# car_v6.net
KiCad netlist of a schematic drawn in EAGLE
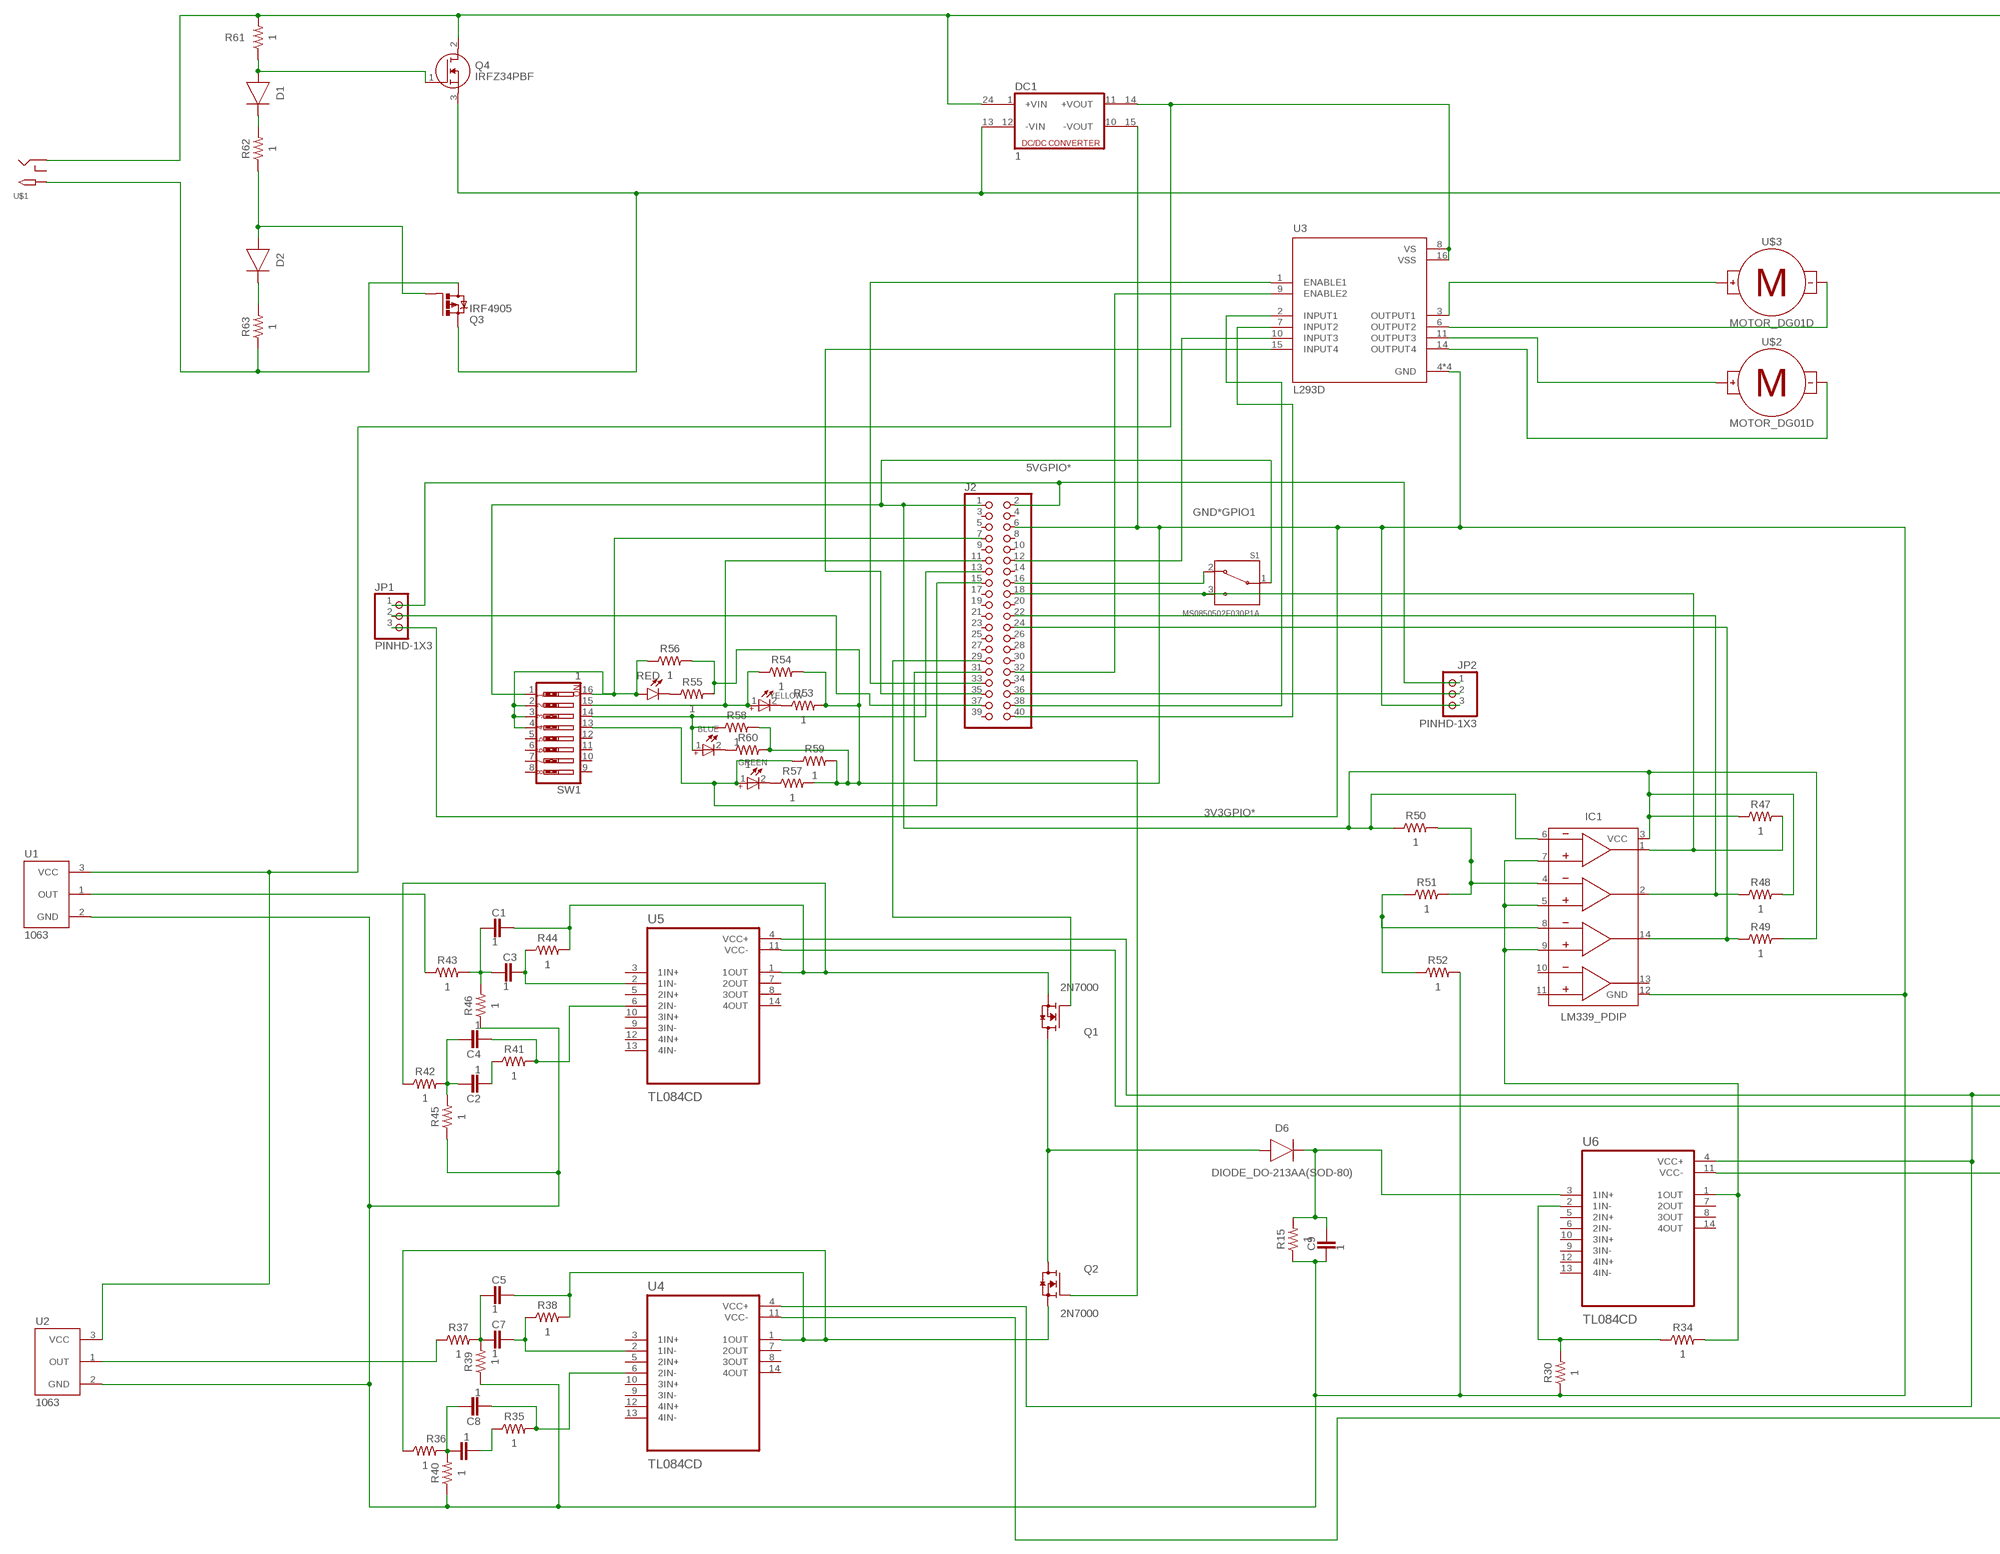
[diagram p0: schematic, sheet 1, part 1 of 2]
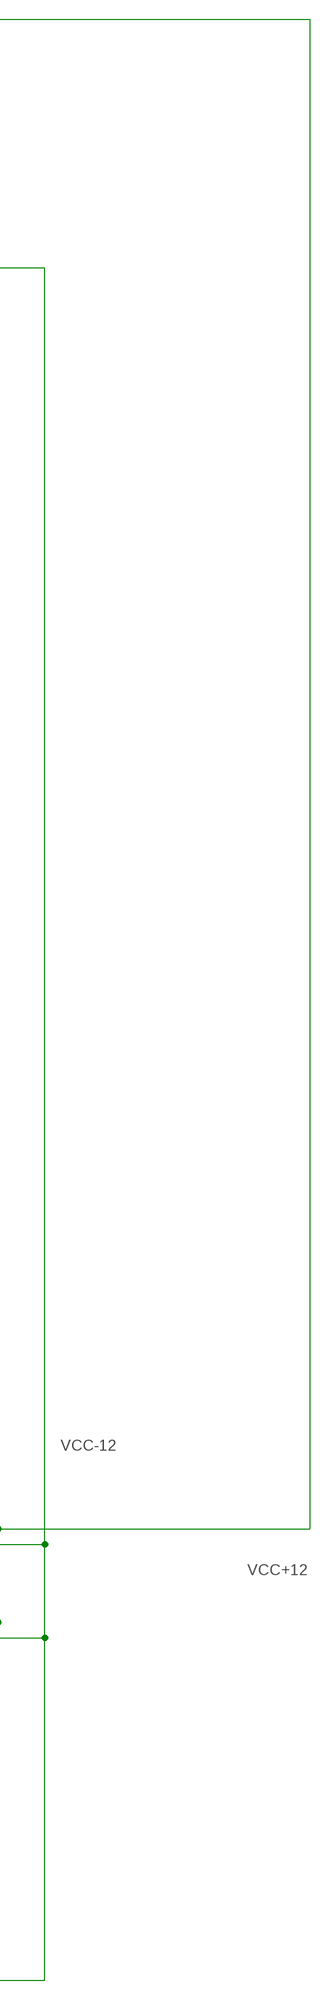
[diagram p1: schematic, sheet 1, part 2 of 2]

(export (version "E")
  (design (tool "Eeschema 10.0.6"))
  (components
    (comp (ref "BLUE")
      (value "WL-TMRC_5MM_WITHOUTSTOPPER")
      (footprint "eagle-import:WL-TMRC_5MM")
      (fields (field (name "MF") "Wurth Electronics") (field (name "MP") "151051BS04000"))
      (libsource (lib "eagle-import") (part "WL-TMRC_5MM_WITHOUTSTOPPER"))
    )
    (comp (ref "C1")
      (value "1")
      (footprint "eagle-import:CAPC1005X60")
      (libsource (lib "eagle-import") (part "CAPACITORCHIP-0402(1005-METRIC)_"))
    )
    (comp (ref "C2")
      (value "1")
      (footprint "eagle-import:CAPC1005X60")
      (libsource (lib "eagle-import") (part "CAPACITORCHIP-0402(1005-METRIC)_"))
    )
    (comp (ref "C3")
      (value "1")
      (footprint "eagle-import:CAPC1005X60")
      (libsource (lib "eagle-import") (part "CAPACITORCHIP-0402(1005-METRIC)_"))
    )
    (comp (ref "C4")
      (value "1")
      (footprint "eagle-import:CAPC1005X60")
      (libsource (lib "eagle-import") (part "CAPACITORCHIP-0402(1005-METRIC)_"))
    )
    (comp (ref "C5")
      (value "1")
      (footprint "eagle-import:CAPC1005X60")
      (libsource (lib "eagle-import") (part "CAPACITORCHIP-0402(1005-METRIC)_"))
    )
    (comp (ref "C6")
      (value "1")
      (footprint "eagle-import:CAPC1005X60")
      (libsource (lib "eagle-import") (part "CAPACITORCHIP-0402(1005-METRIC)_"))
    )
    (comp (ref "C7")
      (value "1")
      (footprint "eagle-import:CAPC1005X60")
      (libsource (lib "eagle-import") (part "CAPACITORCHIP-0402(1005-METRIC)_"))
    )
    (comp (ref "C8")
      (value "1")
      (footprint "eagle-import:CAPC1005X60")
      (libsource (lib "eagle-import") (part "CAPACITORCHIP-0402(1005-METRIC)_"))
    )
    (comp (ref "C9")
      (value "1")
      (footprint "eagle-import:CAPC1005X60")
      (libsource (lib "eagle-import") (part "CAPACITORCHIP-0402(1005-METRIC)_"))
    )
    (comp (ref "D1")
      (value "DIODE_DO-213AA(SOD-80)")
      (footprint "eagle-import:DIOMELF3516")
      (libsource (lib "eagle-import") (part "DIODEDO-213AA(SOD-80)_"))
    )
    (comp (ref "D2")
      (value "DIODE_DO-213AA(SOD-80)")
      (footprint "eagle-import:DIOMELF3516")
      (libsource (lib "eagle-import") (part "DIODEDO-213AA(SOD-80)_"))
    )
    (comp (ref "D6")
      (value "DIODE_DO-213AA(SOD-80)")
      (footprint "eagle-import:DIOMELF3516")
      (libsource (lib "eagle-import") (part "DIODEDO-213AA(SOD-80)_"))
    )
    (comp (ref "DC1")
      (value "1")
      (footprint "eagle-import:CMK")
      (libsource (lib "eagle-import") (part "DC213R"))
    )
    (comp (ref "GREEN")
      (value "WL-TMRC_3MM_WITHOUTSTOPPER")
      (footprint "eagle-import:WL-TMRC_3MM")
      (fields (field (name "MF") "Wurth Electronics") (field (name "MP") "151031VS06000"))
      (libsource (lib "eagle-import") (part "WL-TMRC_3MM_WITHOUTSTOPPER"))
    )
    (comp (ref "IC1")
      (value "LM339_PDIP")
      (footprint "eagle-import:DIP762W53P254L1969H508Q14B")
      (libsource (lib "eagle-import") (part "LM339_PDIP"))
    )
    (comp (ref "J2")
      (value "PiHeaderM")
      (footprint "eagle-import:2X20")
      (libsource (lib "eagle-import") (part "PINHD-2X20"))
    )
    (comp (ref "JP1")
      (value "PINHD-1X3")
      (footprint "eagle-import:1X03")
      (libsource (lib "eagle-import") (part "PINHD-1X3"))
    )
    (comp (ref "JP2")
      (value "PINHD-1X3")
      (footprint "eagle-import:1X03")
      (libsource (lib "eagle-import") (part "PINHD-1X3"))
    )
    (comp (ref "Q1")
      (value "2N7000")
      (footprint "eagle-import:TO92254P458H750-3")
      (fields (field (name "MF") "Diotec Semiconductor"))
      (libsource (lib "eagle-import") (part "2N7000"))
    )
    (comp (ref "Q2")
      (value "2N7000")
      (footprint "eagle-import:TO92254P458H750-3")
      (fields (field (name "MF") "Diotec Semiconductor"))
      (libsource (lib "eagle-import") (part "2N7000"))
    )
    (comp (ref "Q3")
      (value "IRF4905")
      (footprint "eagle-import:TO220BH")
      (fields (field (name "MF") "Infineon Technologies"))
      (libsource (lib "eagle-import") (part "IRF4905"))
    )
    (comp (ref "Q4")
      (value "IRFZ34PBF")
      (footprint "eagle-import:TO254P465X1024X2050-3P")
      (fields (field (name "MOUSER_PART_NUMBER") "844-IRFZ34PBF"))
      (libsource (lib "eagle-import") (part "IRFZ34PBF"))
    )
    (comp (ref "R15")
      (value "1")
      (footprint "eagle-import:RESC1005X40")
      (libsource (lib "eagle-import") (part "R-USCHIP-0402(1005-METRIC)_"))
    )
    (comp (ref "R30")
      (value "1")
      (footprint "eagle-import:RESC1005X40")
      (libsource (lib "eagle-import") (part "R-USCHIP-0402(1005-METRIC)_"))
    )
    (comp (ref "R34")
      (value "1")
      (footprint "eagle-import:RESC1005X40")
      (libsource (lib "eagle-import") (part "R-USCHIP-0402(1005-METRIC)_"))
    )
    (comp (ref "R35")
      (value "1")
      (footprint "eagle-import:RESC1005X40")
      (libsource (lib "eagle-import") (part "R-USCHIP-0402(1005-METRIC)_"))
    )
    (comp (ref "R36")
      (value "1")
      (footprint "eagle-import:RESC1005X40")
      (libsource (lib "eagle-import") (part "R-USCHIP-0402(1005-METRIC)_"))
    )
    (comp (ref "R37")
      (value "1")
      (footprint "eagle-import:RESC1005X40")
      (libsource (lib "eagle-import") (part "R-USCHIP-0402(1005-METRIC)_"))
    )
    (comp (ref "R38")
      (value "1")
      (footprint "eagle-import:RESC1005X40")
      (libsource (lib "eagle-import") (part "R-USCHIP-0402(1005-METRIC)_"))
    )
    (comp (ref "R39")
      (value "1")
      (footprint "eagle-import:RESC1005X40")
      (libsource (lib "eagle-import") (part "R-USCHIP-0402(1005-METRIC)_"))
    )
    (comp (ref "R40")
      (value "1")
      (footprint "eagle-import:RESC1005X40")
      (libsource (lib "eagle-import") (part "R-USCHIP-0402(1005-METRIC)_"))
    )
    (comp (ref "R41")
      (value "1")
      (footprint "eagle-import:RESC1005X40")
      (libsource (lib "eagle-import") (part "R-USCHIP-0402(1005-METRIC)_"))
    )
    (comp (ref "R42")
      (value "1")
      (footprint "eagle-import:RESC1005X40")
      (libsource (lib "eagle-import") (part "R-USCHIP-0402(1005-METRIC)_"))
    )
    (comp (ref "R43")
      (value "1")
      (footprint "eagle-import:RESC1005X40")
      (libsource (lib "eagle-import") (part "R-USCHIP-0402(1005-METRIC)_"))
    )
    (comp (ref "R44")
      (value "1")
      (footprint "eagle-import:RESC1005X40")
      (libsource (lib "eagle-import") (part "R-USCHIP-0402(1005-METRIC)_"))
    )
    (comp (ref "R45")
      (value "1")
      (footprint "eagle-import:RESC1005X40")
      (libsource (lib "eagle-import") (part "R-USCHIP-0402(1005-METRIC)_"))
    )
    (comp (ref "R46")
      (value "1")
      (footprint "eagle-import:RESC1005X40")
      (libsource (lib "eagle-import") (part "R-USCHIP-0402(1005-METRIC)_"))
    )
    (comp (ref "R47")
      (value "1")
      (footprint "eagle-import:RESC1005X40")
      (libsource (lib "eagle-import") (part "R-USCHIP-0402(1005-METRIC)_"))
    )
    (comp (ref "R48")
      (value "1")
      (footprint "eagle-import:RESC1005X40")
      (libsource (lib "eagle-import") (part "R-USCHIP-0402(1005-METRIC)_"))
    )
    (comp (ref "R49")
      (value "1")
      (footprint "eagle-import:RESC1005X40")
      (libsource (lib "eagle-import") (part "R-USCHIP-0402(1005-METRIC)_"))
    )
    (comp (ref "R50")
      (value "1")
      (footprint "eagle-import:RESC1005X40")
      (libsource (lib "eagle-import") (part "R-USCHIP-0402(1005-METRIC)_"))
    )
    (comp (ref "R51")
      (value "1")
      (footprint "eagle-import:RESC1005X40")
      (libsource (lib "eagle-import") (part "R-USCHIP-0402(1005-METRIC)_"))
    )
    (comp (ref "R52")
      (value "1")
      (footprint "eagle-import:RESC1005X40")
      (libsource (lib "eagle-import") (part "R-USCHIP-0402(1005-METRIC)_"))
    )
    (comp (ref "R53")
      (value "1")
      (footprint "eagle-import:RESC1005X40")
      (libsource (lib "eagle-import") (part "R-USCHIP-0402(1005-METRIC)_"))
    )
    (comp (ref "R54")
      (value "1")
      (footprint "eagle-import:RESC1005X40")
      (libsource (lib "eagle-import") (part "R-USCHIP-0402(1005-METRIC)_"))
    )
    (comp (ref "R55")
      (value "1")
      (footprint "eagle-import:RESC1005X40")
      (libsource (lib "eagle-import") (part "R-USCHIP-0402(1005-METRIC)_"))
    )
    (comp (ref "R56")
      (value "1")
      (footprint "eagle-import:RESC1005X40")
      (libsource (lib "eagle-import") (part "R-USCHIP-0402(1005-METRIC)_"))
    )
    (comp (ref "R57")
      (value "1")
      (footprint "eagle-import:RESC1005X40")
      (libsource (lib "eagle-import") (part "R-USCHIP-0402(1005-METRIC)_"))
    )
    (comp (ref "R58")
      (value "1")
      (footprint "eagle-import:RESC1005X40")
      (libsource (lib "eagle-import") (part "R-USCHIP-0402(1005-METRIC)_"))
    )
    (comp (ref "R59")
      (value "1")
      (footprint "eagle-import:RESC1005X40")
      (libsource (lib "eagle-import") (part "R-USCHIP-0402(1005-METRIC)_"))
    )
    (comp (ref "R60")
      (value "1")
      (footprint "eagle-import:RESC1005X40")
      (libsource (lib "eagle-import") (part "R-USCHIP-0402(1005-METRIC)_"))
    )
    (comp (ref "R61")
      (value "1")
      (footprint "eagle-import:RESC1005X40")
      (libsource (lib "eagle-import") (part "R-USCHIP-0402(1005-METRIC)_"))
    )
    (comp (ref "R62")
      (value "1")
      (footprint "eagle-import:RESC1005X40")
      (libsource (lib "eagle-import") (part "R-USCHIP-0402(1005-METRIC)_"))
    )
    (comp (ref "R63")
      (value "1")
      (footprint "eagle-import:RESC1005X40")
      (libsource (lib "eagle-import") (part "R-USCHIP-0402(1005-METRIC)_"))
    )
    (comp (ref "RED")
      (value "LED_RADIALRED")
      (footprint "eagle-import:LEDRD254W60D565H860B_R")
      (libsource (lib "eagle-import") (part "LED_RADIALRED"))
    )
    (comp (ref "S1")
      (value "MS0850502F030P1A")
      (footprint "eagle-import:SW_MS0850502F030P1A")
      (fields (field (name "MF") "E-Switch"))
      (libsource (lib "eagle-import") (part "MS0850502F030P1A"))
    )
    (comp (ref "SW1")
      (value "1")
      (footprint "eagle-import:EDG-08")
      (libsource (lib "eagle-import") (part "SW_DIP-8"))
    )
    (comp (ref "U$1")
      (value "2.1MMJACKTHM")
      (footprint "eagle-import:PJ-102A")
      (libsource (lib "eagle-import") (part "2.1MMJACKTHM"))
    )
    (comp (ref "U$2")
      (value "MOTOR_DG01D")
      (footprint "eagle-import:DG01D")
      (libsource (lib "eagle-import") (part "MOTOR_DG01D"))
    )
    (comp (ref "U$3")
      (value "MOTOR_DG01D")
      (footprint "eagle-import:DG01D")
      (libsource (lib "eagle-import") (part "MOTOR_DG01D"))
    )
    (comp (ref "U1")
      (value "1063")
      (footprint "eagle-import:MODULE_1063")
      (fields (field (name "MF") "Adafruit"))
      (libsource (lib "eagle-import") (part "1063"))
    )
    (comp (ref "U2")
      (value "1063")
      (footprint "eagle-import:MODULE_1063")
      (fields (field (name "MF") "Adafruit"))
      (libsource (lib "eagle-import") (part "1063"))
    )
    (comp (ref "U3")
      (value "L293D")
      (footprint "eagle-import:DIP880W50P254L2000H510Q16")
      (fields (field (name "MF") "STMicroelectronics"))
      (libsource (lib "eagle-import") (part "L293D"))
    )
    (comp (ref "U4")
      (value "TL084CD")
      (footprint "eagle-import:SOIC127P600X175-14N")
      (fields (field (name "DIGIKEY_PART_NUMBER") "296-1285-5-ND") (field (name "MF") "Texas Instruments"))
      (libsource (lib "eagle-import") (part "TL084CD"))
    )
    (comp (ref "U5")
      (value "TL084CD")
      (footprint "eagle-import:SOIC127P600X175-14N")
      (fields (field (name "DIGIKEY_PART_NUMBER") "296-1285-5-ND") (field (name "MF") "Texas Instruments"))
      (libsource (lib "eagle-import") (part "TL084CD"))
    )
    (comp (ref "U6")
      (value "TL084CD")
      (footprint "eagle-import:SOIC127P600X175-14N")
      (fields (field (name "DIGIKEY_PART_NUMBER") "296-1285-5-ND") (field (name "MF") "Texas Instruments"))
      (libsource (lib "eagle-import") (part "TL084CD"))
    )
    (comp (ref "YELLOW")
      (value "WL-TMRC_3MM_WITHOUTSTOPPER")
      (footprint "eagle-import:WL-TMRC_3MM")
      (fields (field (name "MF") "Wurth Electronics") (field (name "MP") "151031YS06000"))
      (libsource (lib "eagle-import") (part "WL-TMRC_3MM-2_WL-TMRC_3MM_WITHOUTSTOPPER"))
    )
  )
  (nets
    (net (code "1") (name "/3V3GPIO*") (class "Default")
      (node (ref "IC1") (pin "3") (pinfunction "VCC_3") (pintype "bidirectional"))
      (node (ref "IC1") (pin "6") (pinfunction "-IN1_6") (pintype "input"))
      (node (ref "J2") (pin "1") (pinfunction "1_1") (pintype "passive"))
      (node (ref "R47") (pin "1") (pinfunction "1_1") (pintype "passive"))
      (node (ref "R48") (pin "2") (pinfunction "2_2") (pintype "passive"))
      (node (ref "R49") (pin "2") (pinfunction "2_2") (pintype "passive"))
      (node (ref "R50") (pin "1") (pinfunction "1_1") (pintype "passive"))
      (node (ref "S1") (pin "1") (pinfunction "COM_1") (pintype "passive"))
      (node (ref "SW1") (pin "1") (pinfunction "1_1") (pintype "passive"))
    )
    (net (code "2") (name "/5VGPIO*") (class "Default")
      (node (ref "J2") (pin "2") (pinfunction "2_2") (pintype "passive"))
      (node (ref "JP1") (pin "1") (pinfunction "1_1") (pintype "passive"))
      (node (ref "JP2") (pin "1") (pinfunction "1_1") (pintype "passive"))
    )
    (net (code "3") (name "/GND*GPIO1") (class "Default")
      (node (ref "C9") (pin "2") (pinfunction "2_2") (pintype "passive"))
      (node (ref "DC1") (pin "15") (pinfunction "-VOUT1_15") (pintype "passive"))
      (node (ref "IC1") (pin "12") (pinfunction "GND_12") (pintype "bidirectional"))
      (node (ref "J2") (pin "6") (pinfunction "6_6") (pintype "passive"))
      (node (ref "JP1") (pin "3") (pinfunction "3_3") (pintype "passive"))
      (node (ref "JP2") (pin "3") (pinfunction "3_3") (pintype "passive"))
      (node (ref "R15") (pin "1") (pinfunction "1_1") (pintype "passive"))
      (node (ref "R30") (pin "1") (pinfunction "1_1") (pintype "passive"))
      (node (ref "R39") (pin "1") (pinfunction "1_1") (pintype "passive"))
      (node (ref "R40") (pin "1") (pinfunction "1_1") (pintype "passive"))
      (node (ref "R45") (pin "1") (pinfunction "1_1") (pintype "passive"))
      (node (ref "R46") (pin "1") (pinfunction "1_1") (pintype "passive"))
      (node (ref "R52") (pin "2") (pinfunction "2_2") (pintype "passive"))
      (node (ref "R53") (pin "2") (pinfunction "2_2") (pintype "passive"))
      (node (ref "R54") (pin "2") (pinfunction "2_2") (pintype "passive"))
      (node (ref "R55") (pin "2") (pinfunction "2_2") (pintype "passive"))
      (node (ref "R56") (pin "2") (pinfunction "2_2") (pintype "passive"))
      (node (ref "R57") (pin "2") (pinfunction "2_2") (pintype "passive"))
      (node (ref "R58") (pin "2") (pinfunction "2_2") (pintype "passive"))
      (node (ref "R59") (pin "2") (pinfunction "2_2") (pintype "passive"))
      (node (ref "R60") (pin "2") (pinfunction "2_2") (pintype "passive"))
      (node (ref "U1") (pin "2") (pinfunction "GND_2") (pintype "power_in"))
      (node (ref "U2") (pin "2") (pinfunction "GND_2") (pintype "power_in"))
      (node (ref "U3") (pin "12") (pinfunction "GND_12") (pintype "power_in"))
      (node (ref "U3") (pin "13") (pinfunction "GND_13") (pintype "power_in"))
      (node (ref "U3") (pin "4") (pinfunction "GND_4") (pintype "power_in"))
      (node (ref "U3") (pin "5") (pinfunction "GND_5") (pintype "power_in"))
    )
    (net (code "4") (name "/VCC+12") (class "Default")
      (node (ref "DC1") (pin "24") (pinfunction "+VIN1_24") (pintype "passive"))
      (node (ref "Q4") (pin "2") (pinfunction "D_2") (pintype "bidirectional"))
      (node (ref "R61") (pin "2") (pinfunction "2_2") (pintype "passive"))
      (node (ref "U$1") (pin "RING") (pinfunction "RING_RING") (pintype "bidirectional"))
      (node (ref "U4") (pin "4") (pinfunction "VCC+_4") (pintype "power_in"))
      (node (ref "U5") (pin "4") (pinfunction "VCC+_4") (pintype "power_in"))
      (node (ref "U6") (pin "4") (pinfunction "VCC+_4") (pintype "power_in"))
    )
    (net (code "5") (name "/VCC-12") (class "Default")
      (node (ref "DC1") (pin "13") (pinfunction "-VIN1_13") (pintype "passive"))
      (node (ref "Q3") (pin "S") (pinfunction "S_S") (pintype "passive"))
      (node (ref "Q4") (pin "3") (pinfunction "S_3") (pintype "bidirectional"))
      (node (ref "U4") (pin "11") (pinfunction "VCC-_11") (pintype "power_in"))
      (node (ref "U5") (pin "11") (pinfunction "VCC-_11") (pintype "power_in"))
      (node (ref "U6") (pin "11") (pinfunction "VCC-_11") (pintype "power_in"))
    )
    (net (code "6") (name "Net-(BLUE-+)") (class "Default")
      (node (ref "BLUE") (pin "1") (pinfunction "+_1") (pintype "passive"))
      (node (ref "J2") (pin "13") (pinfunction "13_13") (pintype "passive"))
      (node (ref "R58") (pin "1") (pinfunction "1_1") (pintype "passive"))
      (node (ref "SW1") (pin "14") (pinfunction "14_14") (pintype "passive"))
    )
    (net (code "7") (name "Net-(BLUE--)") (class "Default")
      (node (ref "BLUE") (pin "2") (pinfunction "-_2") (pintype "passive"))
      (node (ref "R60") (pin "1") (pinfunction "1_1") (pintype "passive"))
    )
    (net (code "8") (name "Net-(C1-Pad2)") (class "Default")
      (node (ref "C1") (pin "2") (pinfunction "2_2") (pintype "passive"))
      (node (ref "C3") (pin "2") (pinfunction "2_2") (pintype "passive"))
      (node (ref "R43") (pin "2") (pinfunction "2_2") (pintype "passive"))
      (node (ref "R46") (pin "2") (pinfunction "2_2") (pintype "passive"))
    )
    (net (code "9") (name "Net-(C2-Pad1)") (class "Default")
      (node (ref "C2") (pin "1") (pinfunction "1_1") (pintype "passive"))
      (node (ref "C4") (pin "1") (pinfunction "1_1") (pintype "passive"))
      (node (ref "R42") (pin "2") (pinfunction "2_2") (pintype "passive"))
      (node (ref "R45") (pin "2") (pinfunction "2_2") (pintype "passive"))
    )
    (net (code "10") (name "Net-(C2-Pad2)") (class "Default")
      (node (ref "C2") (pin "2") (pinfunction "2_2") (pintype "passive"))
      (node (ref "R41") (pin "1") (pinfunction "1_1") (pintype "passive"))
    )
    (net (code "11") (name "Net-(C5-Pad2)") (class "Default")
      (node (ref "C5") (pin "2") (pinfunction "2_2") (pintype "passive"))
      (node (ref "C7") (pin "2") (pinfunction "2_2") (pintype "passive"))
      (node (ref "R37") (pin "2") (pinfunction "2_2") (pintype "passive"))
      (node (ref "R39") (pin "2") (pinfunction "2_2") (pintype "passive"))
    )
    (net (code "12") (name "Net-(C6-Pad1)") (class "Default")
      (node (ref "C6") (pin "1") (pinfunction "1_1") (pintype "passive"))
      (node (ref "C8") (pin "1") (pinfunction "1_1") (pintype "passive"))
      (node (ref "R36") (pin "2") (pinfunction "2_2") (pintype "passive"))
      (node (ref "R40") (pin "2") (pinfunction "2_2") (pintype "passive"))
    )
    (net (code "13") (name "Net-(C6-Pad2)") (class "Default")
      (node (ref "C6") (pin "2") (pinfunction "2_2") (pintype "passive"))
      (node (ref "R35") (pin "1") (pinfunction "1_1") (pintype "passive"))
    )
    (net (code "14") (name "Net-(D1-A)") (class "Default")
      (node (ref "D1") (pin "2") (pinfunction "A_2") (pintype "passive"))
      (node (ref "Q4") (pin "1") (pinfunction "G_1") (pintype "bidirectional"))
      (node (ref "R61") (pin "1") (pinfunction "1_1") (pintype "passive"))
    )
    (net (code "15") (name "Net-(D1-C)") (class "Default")
      (node (ref "D1") (pin "1") (pinfunction "C_1") (pintype "passive"))
      (node (ref "R62") (pin "2") (pinfunction "2_2") (pintype "passive"))
    )
    (net (code "16") (name "Net-(D2-A)") (class "Default")
      (node (ref "D2") (pin "2") (pinfunction "A_2") (pintype "passive"))
      (node (ref "Q3") (pin "G") (pinfunction "G_G") (pintype "passive"))
      (node (ref "R62") (pin "1") (pinfunction "1_1") (pintype "passive"))
    )
    (net (code "17") (name "Net-(D2-C)") (class "Default")
      (node (ref "D2") (pin "1") (pinfunction "C_1") (pintype "passive"))
      (node (ref "R63") (pin "2") (pinfunction "2_2") (pintype "passive"))
    )
    (net (code "18") (name "Net-(D6-A)") (class "Default")
      (node (ref "D6") (pin "2") (pinfunction "A_2") (pintype "passive"))
      (node (ref "Q1") (pin "3") (pinfunction "D_3") (pintype "passive"))
      (node (ref "Q2") (pin "3") (pinfunction "D_3") (pintype "passive"))
    )
    (net (code "19") (name "Net-(D6-C)") (class "Default")
      (node (ref "C9") (pin "1") (pinfunction "1_1") (pintype "passive"))
      (node (ref "D6") (pin "1") (pinfunction "C_1") (pintype "passive"))
      (node (ref "R15") (pin "2") (pinfunction "2_2") (pintype "passive"))
      (node (ref "U6") (pin "3") (pinfunction "1IN+_3") (pintype "input"))
    )
    (net (code "20") (name "Net-(DC1-+VOUT1)") (class "Default")
      (node (ref "DC1") (pin "14") (pinfunction "+VOUT1_14") (pintype "passive"))
      (node (ref "U1") (pin "3") (pinfunction "VCC_3") (pintype "power_in"))
      (node (ref "U2") (pin "3") (pinfunction "VCC_3") (pintype "power_in"))
      (node (ref "U3") (pin "16") (pinfunction "VSS_16") (pintype "power_in"))
      (node (ref "U3") (pin "8") (pinfunction "VS_8") (pintype "power_in"))
    )
    (net (code "21") (name "Net-(GREEN-+)") (class "Default")
      (node (ref "GREEN") (pin "1") (pinfunction "+_1") (pintype "passive"))
      (node (ref "J2") (pin "15") (pinfunction "15_15") (pintype "passive"))
      (node (ref "R59") (pin "1") (pinfunction "1_1") (pintype "passive"))
      (node (ref "SW1") (pin "13") (pinfunction "13_13") (pintype "passive"))
    )
    (net (code "22") (name "Net-(GREEN--)") (class "Default")
      (node (ref "GREEN") (pin "2") (pinfunction "-_2") (pintype "passive"))
      (node (ref "R57") (pin "1") (pinfunction "1_1") (pintype "passive"))
    )
    (net (code "23") (name "Net-(IC1-+IN1)") (class "Default")
      (node (ref "IC1") (pin "5") (pinfunction "+IN2_5") (pintype "input"))
      (node (ref "IC1") (pin "7") (pinfunction "+IN1_7") (pintype "input"))
      (node (ref "IC1") (pin "9") (pinfunction "+IN3_9") (pintype "input"))
      (node (ref "R34") (pin "2") (pinfunction "2_2") (pintype "passive"))
      (node (ref "U6") (pin "1") (pinfunction "1OUT_1") (pintype "output"))
    )
    (net (code "24") (name "Net-(IC1--IN2)") (class "Default")
      (node (ref "IC1") (pin "4") (pinfunction "-IN2_4") (pintype "input"))
      (node (ref "R50") (pin "2") (pinfunction "2_2") (pintype "passive"))
      (node (ref "R51") (pin "2") (pinfunction "2_2") (pintype "passive"))
    )
    (net (code "25") (name "Net-(IC1--IN3)") (class "Default")
      (node (ref "IC1") (pin "8") (pinfunction "-IN3_8") (pintype "input"))
      (node (ref "R51") (pin "1") (pinfunction "1_1") (pintype "passive"))
      (node (ref "R52") (pin "1") (pinfunction "1_1") (pintype "passive"))
    )
    (net (code "26") (name "Net-(IC1-OUT1)") (class "Default")
      (node (ref "IC1") (pin "1") (pinfunction "OUT1_1") (pintype "output"))
      (node (ref "J2") (pin "18") (pinfunction "18_18") (pintype "passive"))
      (node (ref "R47") (pin "2") (pinfunction "2_2") (pintype "passive"))
      (node (ref "S1") (pin "3") (pinfunction "NO_3") (pintype "passive"))
    )
    (net (code "27") (name "Net-(IC1-OUT2)") (class "Default")
      (node (ref "IC1") (pin "2") (pinfunction "OUT2_2") (pintype "output"))
      (node (ref "J2") (pin "22") (pinfunction "22_22") (pintype "passive"))
      (node (ref "R48") (pin "1") (pinfunction "1_1") (pintype "passive"))
    )
    (net (code "28") (name "Net-(IC1-OUT3)") (class "Default")
      (node (ref "IC1") (pin "14") (pinfunction "OUT3_14") (pintype "output"))
      (node (ref "J2") (pin "24") (pinfunction "24_24") (pintype "passive"))
      (node (ref "R49") (pin "1") (pinfunction "1_1") (pintype "passive"))
    )
    (net (code "29") (name "Net-(J2-Pad7)") (class "Default")
      (node (ref "J2") (pin "7") (pinfunction "7_7") (pintype "passive"))
      (node (ref "R56") (pin "1") (pinfunction "1_1") (pintype "passive"))
      (node (ref "RED") (pin "A") (pinfunction "A_A") (pintype "passive"))
      (node (ref "SW1") (pin "16") (pinfunction "16_16") (pintype "passive"))
      (node (ref "SW1") (pin "2") (pinfunction "2_2") (pintype "passive"))
      (node (ref "SW1") (pin "3") (pinfunction "3_3") (pintype "passive"))
      (node (ref "SW1") (pin "4") (pinfunction "4_4") (pintype "passive"))
    )
    (net (code "30") (name "Net-(J2-Pad36)") (class "Default")
      (node (ref "J2") (pin "36") (pinfunction "36_36") (pintype "passive"))
      (node (ref "JP2") (pin "2") (pinfunction "2_2") (pintype "passive"))
    )
    (net (code "31") (name "Net-(J2-Pad37)") (class "Default")
      (node (ref "J2") (pin "37") (pinfunction "37_37") (pintype "passive"))
      (node (ref "JP1") (pin "2") (pinfunction "2_2") (pintype "passive"))
    )
    (net (code "32") (name "Net-(Q1-G)") (class "Default")
      (node (ref "J2") (pin "29") (pinfunction "29_29") (pintype "passive"))
      (node (ref "Q1") (pin "2") (pinfunction "G_2") (pintype "passive"))
    )
    (net (code "33") (name "Net-(Q1-S)") (class "Default")
      (node (ref "C1") (pin "1") (pinfunction "1_1") (pintype "passive"))
      (node (ref "Q1") (pin "1") (pinfunction "S_1") (pintype "passive"))
      (node (ref "R42") (pin "1") (pinfunction "1_1") (pintype "passive"))
      (node (ref "R44") (pin "2") (pinfunction "2_2") (pintype "passive"))
      (node (ref "U5") (pin "1") (pinfunction "1OUT_1") (pintype "output"))
    )
    (net (code "34") (name "Net-(Q2-G)") (class "Default")
      (node (ref "J2") (pin "31") (pinfunction "31_31") (pintype "passive"))
      (node (ref "Q2") (pin "2") (pinfunction "G_2") (pintype "passive"))
    )
    (net (code "35") (name "Net-(Q2-S)") (class "Default")
      (node (ref "C5") (pin "1") (pinfunction "1_1") (pintype "passive"))
      (node (ref "Q2") (pin "1") (pinfunction "S_1") (pintype "passive"))
      (node (ref "R36") (pin "1") (pinfunction "1_1") (pintype "passive"))
      (node (ref "R38") (pin "2") (pinfunction "2_2") (pintype "passive"))
      (node (ref "U4") (pin "1") (pinfunction "1OUT_1") (pintype "output"))
    )
    (net (code "36") (name "Net-(Q3-PadD)") (class "Default")
      (node (ref "Q3") (pin "D") (pinfunction "D_D") (pintype "passive"))
      (node (ref "R63") (pin "1") (pinfunction "1_1") (pintype "passive"))
      (node (ref "U$1") (pin "TIP") (pinfunction "TIP_TIP") (pintype "bidirectional"))
    )
    (net (code "37") (name "Net-(R55-Pad1)") (class "Default")
      (node (ref "R55") (pin "1") (pinfunction "1_1") (pintype "passive"))
      (node (ref "RED") (pin "C") (pinfunction "C_C") (pintype "passive"))
    )
    (net (code "38") (name "Net-(S1-NC)") (class "Default")
      (node (ref "J2") (pin "16") (pinfunction "16_16") (pintype "passive"))
      (node (ref "S1") (pin "2") (pinfunction "NC_2") (pintype "passive"))
    )
    (net (code "39") (name "Net-(U1-OUT)") (class "Default")
      (node (ref "R43") (pin "1") (pinfunction "1_1") (pintype "passive"))
      (node (ref "U1") (pin "1") (pinfunction "OUT_1") (pintype "output"))
    )
    (net (code "40") (name "Net-(U2-OUT)") (class "Default")
      (node (ref "R37") (pin "1") (pinfunction "1_1") (pintype "passive"))
      (node (ref "U2") (pin "1") (pinfunction "OUT_1") (pintype "output"))
    )
    (net (code "41") (name "Net-(U3-ENABLE1)") (class "Default")
      (node (ref "J2") (pin "33") (pinfunction "33_33") (pintype "passive"))
      (node (ref "U3") (pin "1") (pinfunction "ENABLE1_1") (pintype "input"))
    )
    (net (code "42") (name "Net-(U3-ENABLE2)") (class "Default")
      (node (ref "J2") (pin "32") (pinfunction "32_32") (pintype "passive"))
      (node (ref "U3") (pin "9") (pinfunction "ENABLE2_9") (pintype "input"))
    )
    (net (code "43") (name "Net-(U3-INPUT1)") (class "Default")
      (node (ref "J2") (pin "38") (pinfunction "38_38") (pintype "passive"))
      (node (ref "U3") (pin "2") (pinfunction "INPUT1_2") (pintype "input"))
    )
    (net (code "44") (name "Net-(U3-INPUT2)") (class "Default")
      (node (ref "J2") (pin "40") (pinfunction "40_40") (pintype "passive"))
      (node (ref "U3") (pin "7") (pinfunction "INPUT2_7") (pintype "input"))
    )
    (net (code "45") (name "Net-(U3-INPUT3)") (class "Default")
      (node (ref "J2") (pin "12") (pinfunction "12_12") (pintype "passive"))
      (node (ref "U3") (pin "10") (pinfunction "INPUT3_10") (pintype "input"))
    )
    (net (code "46") (name "Net-(U3-INPUT4)") (class "Default")
      (node (ref "J2") (pin "35") (pinfunction "35_35") (pintype "passive"))
      (node (ref "U3") (pin "15") (pinfunction "INPUT4_15") (pintype "input"))
    )
    (net (code "47") (name "Net-(U3-OUTPUT1)") (class "Default")
      (node (ref "U$3") (pin "+") (pinfunction "+_+") (pintype "passive"))
      (node (ref "U3") (pin "3") (pinfunction "OUTPUT1_3") (pintype "output"))
    )
    (net (code "48") (name "Net-(U3-OUTPUT2)") (class "Default")
      (node (ref "U$3") (pin "-") (pinfunction "-_-") (pintype "passive"))
      (node (ref "U3") (pin "6") (pinfunction "OUTPUT2_6") (pintype "output"))
    )
    (net (code "49") (name "Net-(U3-OUTPUT3)") (class "Default")
      (node (ref "U$2") (pin "+") (pinfunction "+_+") (pintype "passive"))
      (node (ref "U3") (pin "11") (pinfunction "OUTPUT3_11") (pintype "output"))
    )
    (net (code "50") (name "Net-(U3-OUTPUT4)") (class "Default")
      (node (ref "U$2") (pin "-") (pinfunction "-_-") (pintype "passive"))
      (node (ref "U3") (pin "14") (pinfunction "OUTPUT4_14") (pintype "output"))
    )
    (net (code "51") (name "Net-(U4-1IN-)") (class "Default")
      (node (ref "C7") (pin "1") (pinfunction "1_1") (pintype "passive"))
      (node (ref "R38") (pin "1") (pinfunction "1_1") (pintype "passive"))
      (node (ref "U4") (pin "2") (pinfunction "1IN-_2") (pintype "input"))
    )
    (net (code "52") (name "Net-(U4-2IN-)") (class "Default")
      (node (ref "C8") (pin "2") (pinfunction "2_2") (pintype "passive"))
      (node (ref "R35") (pin "2") (pinfunction "2_2") (pintype "passive"))
      (node (ref "U4") (pin "6") (pinfunction "2IN-_6") (pintype "input"))
    )
    (net (code "53") (name "Net-(U5-1IN-)") (class "Default")
      (node (ref "C3") (pin "1") (pinfunction "1_1") (pintype "passive"))
      (node (ref "R44") (pin "1") (pinfunction "1_1") (pintype "passive"))
      (node (ref "U5") (pin "2") (pinfunction "1IN-_2") (pintype "input"))
    )
    (net (code "54") (name "Net-(U5-2IN-)") (class "Default")
      (node (ref "C4") (pin "2") (pinfunction "2_2") (pintype "passive"))
      (node (ref "R41") (pin "2") (pinfunction "2_2") (pintype "passive"))
      (node (ref "U5") (pin "6") (pinfunction "2IN-_6") (pintype "input"))
    )
    (net (code "55") (name "Net-(U6-1IN-)") (class "Default")
      (node (ref "R30") (pin "2") (pinfunction "2_2") (pintype "passive"))
      (node (ref "R34") (pin "1") (pinfunction "1_1") (pintype "passive"))
      (node (ref "U6") (pin "2") (pinfunction "1IN-_2") (pintype "input"))
    )
    (net (code "56") (name "Net-(YELLOW-+)") (class "Default")
      (node (ref "J2") (pin "11") (pinfunction "11_11") (pintype "passive"))
      (node (ref "R54") (pin "1") (pinfunction "1_1") (pintype "passive"))
      (node (ref "SW1") (pin "15") (pinfunction "15_15") (pintype "passive"))
      (node (ref "YELLOW") (pin "1") (pinfunction "+_1") (pintype "passive"))
    )
    (net (code "57") (name "Net-(YELLOW--)") (class "Default")
      (node (ref "R53") (pin "1") (pinfunction "1_1") (pintype "passive"))
      (node (ref "YELLOW") (pin "2") (pinfunction "-_2") (pintype "passive"))
    )
    (net (code "58") (name "unconnected-(DC1-+VIN-Pad1)") (class "Default")
      (node (ref "DC1") (pin "1") (pinfunction "+VIN_1") (pintype "passive"))
    )
    (net (code "59") (name "unconnected-(DC1-+VOUT-Pad11)") (class "Default")
      (node (ref "DC1") (pin "11") (pinfunction "+VOUT_11") (pintype "passive"))
    )
    (net (code "60") (name "unconnected-(DC1--VIN-Pad12)") (class "Default")
      (node (ref "DC1") (pin "12") (pinfunction "-VIN_12") (pintype "passive"))
    )
    (net (code "61") (name "unconnected-(DC1--VOUT-Pad10)") (class "Default")
      (node (ref "DC1") (pin "10") (pinfunction "-VOUT_10") (pintype "passive"))
    )
    (net (code "62") (name "unconnected-(IC1-+IN4-Pad11)") (class "Default")
      (node (ref "IC1") (pin "11") (pinfunction "+IN4_11") (pintype "input"))
    )
    (net (code "63") (name "unconnected-(IC1--IN4-Pad10)") (class "Default")
      (node (ref "IC1") (pin "10") (pinfunction "-IN4_10") (pintype "input"))
    )
    (net (code "64") (name "unconnected-(IC1-OUT4-Pad13)") (class "Default")
      (node (ref "IC1") (pin "13") (pinfunction "OUT4_13") (pintype "output"))
    )
    (net (code "65") (name "unconnected-(J2-Pad3)") (class "Default")
      (node (ref "J2") (pin "3") (pinfunction "3_3") (pintype "passive"))
    )
    (net (code "66") (name "unconnected-(J2-Pad4)") (class "Default")
      (node (ref "J2") (pin "4") (pinfunction "4_4") (pintype "passive"))
    )
    (net (code "67") (name "unconnected-(J2-Pad5)") (class "Default")
      (node (ref "J2") (pin "5") (pinfunction "5_5") (pintype "passive"))
    )
    (net (code "68") (name "unconnected-(J2-Pad8)") (class "Default")
      (node (ref "J2") (pin "8") (pinfunction "8_8") (pintype "passive"))
    )
    (net (code "69") (name "unconnected-(J2-Pad9)") (class "Default")
      (node (ref "J2") (pin "9") (pinfunction "9_9") (pintype "passive"))
    )
    (net (code "70") (name "unconnected-(J2-Pad10)") (class "Default")
      (node (ref "J2") (pin "10") (pinfunction "10_10") (pintype "passive"))
    )
    (net (code "71") (name "unconnected-(J2-Pad14)") (class "Default")
      (node (ref "J2") (pin "14") (pinfunction "14_14") (pintype "passive"))
    )
    (net (code "72") (name "unconnected-(J2-Pad17)") (class "Default")
      (node (ref "J2") (pin "17") (pinfunction "17_17") (pintype "passive"))
    )
    (net (code "73") (name "unconnected-(J2-Pad19)") (class "Default")
      (node (ref "J2") (pin "19") (pinfunction "19_19") (pintype "passive"))
    )
    (net (code "74") (name "unconnected-(J2-Pad20)") (class "Default")
      (node (ref "J2") (pin "20") (pinfunction "20_20") (pintype "passive"))
    )
    (net (code "75") (name "unconnected-(J2-Pad21)") (class "Default")
      (node (ref "J2") (pin "21") (pinfunction "21_21") (pintype "passive"))
    )
    (net (code "76") (name "unconnected-(J2-Pad23)") (class "Default")
      (node (ref "J2") (pin "23") (pinfunction "23_23") (pintype "passive"))
    )
    (net (code "77") (name "unconnected-(J2-Pad25)") (class "Default")
      (node (ref "J2") (pin "25") (pinfunction "25_25") (pintype "passive"))
    )
    (net (code "78") (name "unconnected-(J2-Pad26)") (class "Default")
      (node (ref "J2") (pin "26") (pinfunction "26_26") (pintype "passive"))
    )
    (net (code "79") (name "unconnected-(J2-Pad27)") (class "Default")
      (node (ref "J2") (pin "27") (pinfunction "27_27") (pintype "passive"))
    )
    (net (code "80") (name "unconnected-(J2-Pad28)") (class "Default")
      (node (ref "J2") (pin "28") (pinfunction "28_28") (pintype "passive"))
    )
    (net (code "81") (name "unconnected-(J2-Pad30)") (class "Default")
      (node (ref "J2") (pin "30") (pinfunction "30_30") (pintype "passive"))
    )
    (net (code "82") (name "unconnected-(J2-Pad34)") (class "Default")
      (node (ref "J2") (pin "34") (pinfunction "34_34") (pintype "passive"))
    )
    (net (code "83") (name "unconnected-(J2-Pad39)") (class "Default")
      (node (ref "J2") (pin "39") (pinfunction "39_39") (pintype "passive"))
    )
    (net (code "84") (name "unconnected-(SW1-Pad5)") (class "Default")
      (node (ref "SW1") (pin "5") (pinfunction "5_5") (pintype "passive"))
    )
    (net (code "85") (name "unconnected-(SW1-Pad6)") (class "Default")
      (node (ref "SW1") (pin "6") (pinfunction "6_6") (pintype "passive"))
    )
    (net (code "86") (name "unconnected-(SW1-Pad7)") (class "Default")
      (node (ref "SW1") (pin "7") (pinfunction "7_7") (pintype "passive"))
    )
    (net (code "87") (name "unconnected-(SW1-Pad8)") (class "Default")
      (node (ref "SW1") (pin "8") (pinfunction "8_8") (pintype "passive"))
    )
    (net (code "88") (name "unconnected-(SW1-Pad9)") (class "Default")
      (node (ref "SW1") (pin "9") (pinfunction "9_9") (pintype "passive"))
    )
    (net (code "89") (name "unconnected-(SW1-Pad10)") (class "Default")
      (node (ref "SW1") (pin "10") (pinfunction "10_10") (pintype "passive"))
    )
    (net (code "90") (name "unconnected-(SW1-Pad11)") (class "Default")
      (node (ref "SW1") (pin "11") (pinfunction "11_11") (pintype "passive"))
    )
    (net (code "91") (name "unconnected-(SW1-Pad12)") (class "Default")
      (node (ref "SW1") (pin "12") (pinfunction "12_12") (pintype "passive"))
    )
    (net (code "92") (name "unconnected-(U$1-PadRING_SW)") (class "Default")
      (node (ref "U$1") (pin "RING_SW") (pinfunction "RING_SW_RING_SW") (pintype "bidirectional"))
    )
    (net (code "93") (name "unconnected-(U4-1IN+-Pad3)") (class "Default")
      (node (ref "U4") (pin "3") (pinfunction "1IN+_3") (pintype "input"))
    )
    (net (code "94") (name "unconnected-(U4-2IN+-Pad5)") (class "Default")
      (node (ref "U4") (pin "5") (pinfunction "2IN+_5") (pintype "input"))
    )
    (net (code "95") (name "unconnected-(U4-2OUT-Pad7)") (class "Default")
      (node (ref "U4") (pin "7") (pinfunction "2OUT_7") (pintype "output"))
    )
    (net (code "96") (name "unconnected-(U4-3IN+-Pad10)") (class "Default")
      (node (ref "U4") (pin "10") (pinfunction "3IN+_10") (pintype "input"))
    )
    (net (code "97") (name "unconnected-(U4-3IN--Pad9)") (class "Default")
      (node (ref "U4") (pin "9") (pinfunction "3IN-_9") (pintype "input"))
    )
    (net (code "98") (name "unconnected-(U4-3OUT-Pad8)") (class "Default")
      (node (ref "U4") (pin "8") (pinfunction "3OUT_8") (pintype "output"))
    )
    (net (code "99") (name "unconnected-(U4-4IN+-Pad12)") (class "Default")
      (node (ref "U4") (pin "12") (pinfunction "4IN+_12") (pintype "input"))
    )
    (net (code "100") (name "unconnected-(U4-4IN--Pad13)") (class "Default")
      (node (ref "U4") (pin "13") (pinfunction "4IN-_13") (pintype "input"))
    )
    (net (code "101") (name "unconnected-(U4-4OUT-Pad14)") (class "Default")
      (node (ref "U4") (pin "14") (pinfunction "4OUT_14") (pintype "output"))
    )
    (net (code "102") (name "unconnected-(U5-1IN+-Pad3)") (class "Default")
      (node (ref "U5") (pin "3") (pinfunction "1IN+_3") (pintype "input"))
    )
    (net (code "103") (name "unconnected-(U5-2IN+-Pad5)") (class "Default")
      (node (ref "U5") (pin "5") (pinfunction "2IN+_5") (pintype "input"))
    )
    (net (code "104") (name "unconnected-(U5-2OUT-Pad7)") (class "Default")
      (node (ref "U5") (pin "7") (pinfunction "2OUT_7") (pintype "output"))
    )
    (net (code "105") (name "unconnected-(U5-3IN+-Pad10)") (class "Default")
      (node (ref "U5") (pin "10") (pinfunction "3IN+_10") (pintype "input"))
    )
    (net (code "106") (name "unconnected-(U5-3IN--Pad9)") (class "Default")
      (node (ref "U5") (pin "9") (pinfunction "3IN-_9") (pintype "input"))
    )
    (net (code "107") (name "unconnected-(U5-3OUT-Pad8)") (class "Default")
      (node (ref "U5") (pin "8") (pinfunction "3OUT_8") (pintype "output"))
    )
    (net (code "108") (name "unconnected-(U5-4IN+-Pad12)") (class "Default")
      (node (ref "U5") (pin "12") (pinfunction "4IN+_12") (pintype "input"))
    )
    (net (code "109") (name "unconnected-(U5-4IN--Pad13)") (class "Default")
      (node (ref "U5") (pin "13") (pinfunction "4IN-_13") (pintype "input"))
    )
    (net (code "110") (name "unconnected-(U5-4OUT-Pad14)") (class "Default")
      (node (ref "U5") (pin "14") (pinfunction "4OUT_14") (pintype "output"))
    )
    (net (code "111") (name "unconnected-(U6-2IN+-Pad5)") (class "Default")
      (node (ref "U6") (pin "5") (pinfunction "2IN+_5") (pintype "input"))
    )
    (net (code "112") (name "unconnected-(U6-2IN--Pad6)") (class "Default")
      (node (ref "U6") (pin "6") (pinfunction "2IN-_6") (pintype "input"))
    )
    (net (code "113") (name "unconnected-(U6-2OUT-Pad7)") (class "Default")
      (node (ref "U6") (pin "7") (pinfunction "2OUT_7") (pintype "output"))
    )
    (net (code "114") (name "unconnected-(U6-3IN+-Pad10)") (class "Default")
      (node (ref "U6") (pin "10") (pinfunction "3IN+_10") (pintype "input"))
    )
    (net (code "115") (name "unconnected-(U6-3IN--Pad9)") (class "Default")
      (node (ref "U6") (pin "9") (pinfunction "3IN-_9") (pintype "input"))
    )
    (net (code "116") (name "unconnected-(U6-3OUT-Pad8)") (class "Default")
      (node (ref "U6") (pin "8") (pinfunction "3OUT_8") (pintype "output"))
    )
    (net (code "117") (name "unconnected-(U6-4IN+-Pad12)") (class "Default")
      (node (ref "U6") (pin "12") (pinfunction "4IN+_12") (pintype "input"))
    )
    (net (code "118") (name "unconnected-(U6-4IN--Pad13)") (class "Default")
      (node (ref "U6") (pin "13") (pinfunction "4IN-_13") (pintype "input"))
    )
    (net (code "119") (name "unconnected-(U6-4OUT-Pad14)") (class "Default")
      (node (ref "U6") (pin "14") (pinfunction "4OUT_14") (pintype "output"))
    )
  )
)
